# 04.net
KiCad netlist of a schematic drawn in Altium Designer
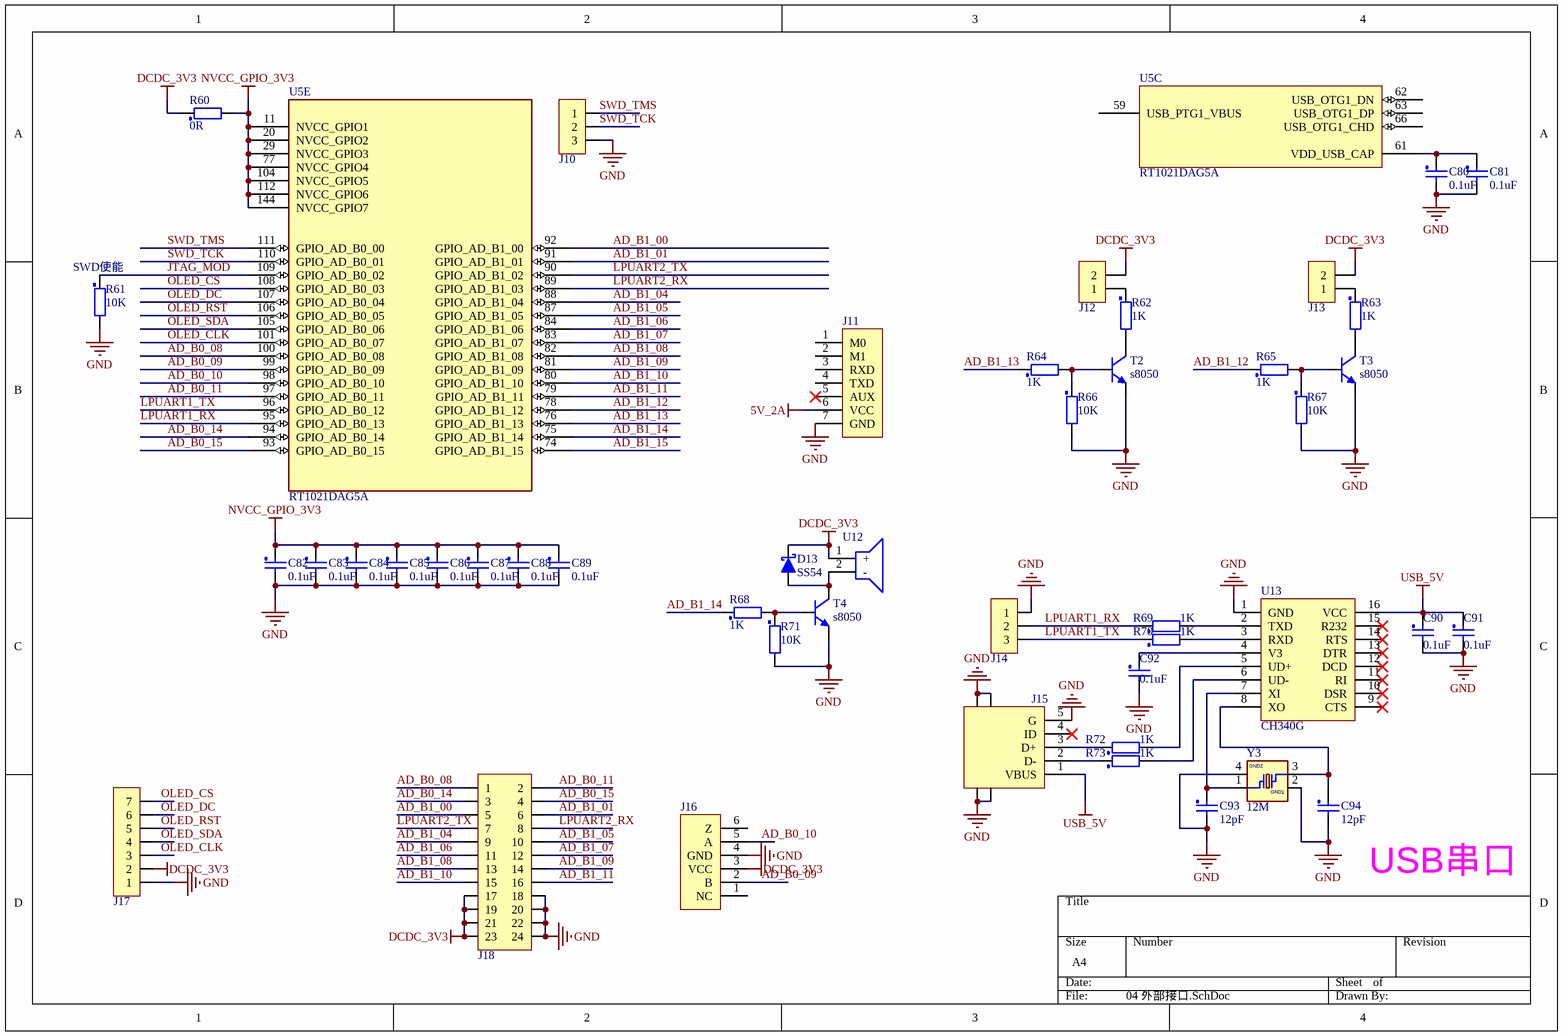
[diagram p0: 04 外部接口.SchDoc]

(export (version "E")
  (design (tool "Eeschema 10.0.6"))
  (components
    (comp (ref "C80")
      (value "0.1uF")
      (footprint "cap0603")
      (description "贴片电容")
      (fields (field (name "PUBLISHER") "Altium Limited"))
      (libsource (lib "元件库") (part "Cap"))
    )
    (comp (ref "C81")
      (value "0.1uF")
      (footprint "cap0603")
      (description "贴片电容")
      (fields (field (name "PUBLISHER") "Altium Limited"))
      (libsource (lib "元件库") (part "Cap"))
    )
    (comp (ref "C82")
      (value "0.1uF")
      (footprint "cap0603")
      (description "贴片电容")
      (fields (field (name "PUBLISHER") "Altium Limited"))
      (libsource (lib "元件库") (part "Cap"))
    )
    (comp (ref "C83")
      (value "0.1uF")
      (footprint "cap0603")
      (description "贴片电容")
      (fields (field (name "PUBLISHER") "Altium Limited"))
      (libsource (lib "元件库") (part "Cap"))
    )
    (comp (ref "C84")
      (value "0.1uF")
      (footprint "cap0603")
      (description "贴片电容")
      (fields (field (name "PUBLISHER") "Altium Limited"))
      (libsource (lib "元件库") (part "Cap"))
    )
    (comp (ref "C85")
      (value "0.1uF")
      (footprint "cap0603")
      (description "贴片电容")
      (fields (field (name "PUBLISHER") "Altium Limited"))
      (libsource (lib "元件库") (part "Cap"))
    )
    (comp (ref "C86")
      (value "0.1uF")
      (footprint "cap0603")
      (description "贴片电容")
      (fields (field (name "PUBLISHER") "Altium Limited"))
      (libsource (lib "元件库") (part "Cap"))
    )
    (comp (ref "C87")
      (value "0.1uF")
      (footprint "cap0603")
      (description "贴片电容")
      (fields (field (name "PUBLISHER") "Altium Limited"))
      (libsource (lib "元件库") (part "Cap"))
    )
    (comp (ref "C88")
      (value "0.1uF")
      (footprint "cap0603")
      (description "贴片电容")
      (fields (field (name "PUBLISHER") "Altium Limited"))
      (libsource (lib "元件库") (part "Cap"))
    )
    (comp (ref "C89")
      (value "0.1uF")
      (footprint "cap0603")
      (description "贴片电容")
      (fields (field (name "PUBLISHER") "Altium Limited"))
      (libsource (lib "元件库") (part "Cap"))
    )
    (comp (ref "C90")
      (value "0.1uF")
      (footprint "cap0603")
      (description "贴片电容")
      (fields (field (name "PUBLISHER") "Altium Limited"))
      (libsource (lib "元件库") (part "Cap"))
    )
    (comp (ref "C91")
      (value "0.1uF")
      (footprint "cap0603")
      (description "贴片电容")
      (fields (field (name "PUBLISHER") "Altium Limited"))
      (libsource (lib "元件库") (part "Cap"))
    )
    (comp (ref "C92")
      (value "0.1uF")
      (footprint "cap0603")
      (description "贴片电容")
      (fields (field (name "PUBLISHER") "Altium Limited"))
      (libsource (lib "元件库") (part "Cap"))
    )
    (comp (ref "C93")
      (value "12pF")
      (footprint "cap0603")
      (description "贴片电容")
      (fields (field (name "PUBLISHER") "Altium Limited"))
      (libsource (lib "元件库") (part "Cap"))
    )
    (comp (ref "C94")
      (value "12pF")
      (footprint "cap0603")
      (description "贴片电容")
      (fields (field (name "PUBLISHER") "Altium Limited"))
      (libsource (lib "元件库") (part "Cap"))
    )
    (comp (ref "D13")
      (value "SS54")
      (footprint "SMA(DO-214AC)")
      (description "肖特基二极管")
      (fields (field (name "PUBLISHER") "Altium Limited"))
      (libsource (lib "元件库") (part "D Schottky"))
    )
    (comp (ref "J10")
      (value "1X3")
      (footprint "HDR-1X3_SWD")
      (description "2.54mm公排针")
      (fields (field (name "版权归属") "源创客"))
      (libsource (lib "元件库") (part "Header 3"))
    )
    (comp (ref "J11")
      (value "1x7m")
      (footprint "uart_nrf24l01")
      (description "2.54mm母排座")
      (libsource (lib "元件库") (part "无线串口模块"))
    )
    (comp (ref "J12")
      (value "1x2")
      (footprint "HDR-1X2")
      (description "2.54mm公排针")
      (fields (field (name "版权归属") "源创客"))
      (libsource (lib "元件库") (part "Header 2"))
    )
    (comp (ref "J13")
      (value "1x2")
      (footprint "HDR-1X2")
      (description "2.54mm公排针")
      (fields (field (name "版权归属") "源创客"))
      (libsource (lib "元件库") (part "Header 2"))
    )
    (comp (ref "J14")
      (value "1X3")
      (footprint "HDR-1X3")
      (description "2.54mm公排针")
      (fields (field (name "版权归属") "源创客"))
      (libsource (lib "元件库") (part "Header 3"))
    )
    (comp (ref "J15")
      (value "USB_micro_b")
      (footprint "USB_micro_b")
      (description "microUSB母座,立创商城C404969")
      (libsource (lib "元件库") (part "USB_micro_b"))
    )
    (comp (ref "J16")
      (value "2x3")
      (footprint "LQ256Encoder")
      (description "2.54mm公排针")
      (libsource (lib "元件库") (part "LQ_AB256"))
    )
    (comp (ref "J17")
      (value "1X5m")
      (footprint "LQ_OLED128X64去丝印")
      (description "2.54mm母排座")
      (fields (field (name "版权归属") "源创客"))
      (libsource (lib "元件库") (part "Header 7"))
    )
    (comp (ref "J18")
      (value "2x12")
      (footprint "HDR-2x12")
      (description "2.54mm公排针")
      (fields (field (name "版权归属") "源创客"))
      (libsource (lib "元件库") (part "Header 12*2"))
    )
    (comp (ref "R60")
      (value "0R")
      (footprint "res0603")
      (description "贴片电阻")
      (fields (field (name "PUBLISHER") "Altium Limited"))
      (libsource (lib "") (part "Res_1"))
    )
    (comp (ref "R61")
      (value "10K")
      (footprint "res0603")
      (description "贴片电阻")
      (fields (field (name "PUBLISHER") "Altium Limited"))
      (libsource (lib "元件库") (part "Res"))
    )
    (comp (ref "R62")
      (value "1K")
      (footprint "res0603")
      (description "贴片电阻")
      (fields (field (name "PUBLISHER") "Altium Limited"))
      (libsource (lib "元件库") (part "Res"))
    )
    (comp (ref "R63")
      (value "1K")
      (footprint "res0603")
      (description "贴片电阻")
      (fields (field (name "PUBLISHER") "Altium Limited"))
      (libsource (lib "元件库") (part "Res"))
    )
    (comp (ref "R64")
      (value "1K")
      (footprint "res0603")
      (description "贴片电阻")
      (fields (field (name "PUBLISHER") "Altium Limited"))
      (libsource (lib "") (part "Res_1"))
    )
    (comp (ref "R65")
      (value "1K")
      (footprint "res0603")
      (description "贴片电阻")
      (fields (field (name "PUBLISHER") "Altium Limited"))
      (libsource (lib "") (part "Res_1"))
    )
    (comp (ref "R66")
      (value "10K")
      (footprint "res0603")
      (description "贴片电阻")
      (fields (field (name "PUBLISHER") "Altium Limited"))
      (libsource (lib "元件库") (part "Res"))
    )
    (comp (ref "R67")
      (value "10K")
      (footprint "res0603")
      (description "贴片电阻")
      (fields (field (name "PUBLISHER") "Altium Limited"))
      (libsource (lib "元件库") (part "Res"))
    )
    (comp (ref "R68")
      (value "1K")
      (footprint "res0603")
      (description "贴片电阻")
      (fields (field (name "PUBLISHER") "Altium Limited"))
      (libsource (lib "") (part "Res_1"))
    )
    (comp (ref "R69")
      (value "1K")
      (footprint "res0603")
      (description "贴片电阻")
      (fields (field (name "PUBLISHER") "Altium Limited"))
      (libsource (lib "") (part "Res_1"))
    )
    (comp (ref "R70")
      (value "1K")
      (footprint "res0603")
      (description "贴片电阻")
      (fields (field (name "PUBLISHER") "Altium Limited"))
      (libsource (lib "") (part "Res_1"))
    )
    (comp (ref "R71")
      (value "10K")
      (footprint "res0603")
      (description "贴片电阻")
      (fields (field (name "PUBLISHER") "Altium Limited"))
      (libsource (lib "元件库") (part "Res"))
    )
    (comp (ref "R72")
      (value "1K")
      (footprint "res0603")
      (description "贴片电阻")
      (fields (field (name "PUBLISHER") "Altium Limited"))
      (libsource (lib "") (part "Res_1"))
    )
    (comp (ref "R73")
      (value "1K")
      (footprint "res0603")
      (description "贴片电阻")
      (fields (field (name "PUBLISHER") "Altium Limited"))
      (libsource (lib "") (part "Res_1"))
    )
    (comp (ref "T2")
      (value "s8050")
      (footprint "SOT-23-3")
      (description "贴片三极管 NPN管")
      (libsource (lib "元件库") (part "s8050"))
    )
    (comp (ref "T3")
      (value "s8050")
      (footprint "SOT-23-3")
      (description "贴片三极管 NPN管")
      (libsource (lib "元件库") (part "s8050"))
    )
    (comp (ref "T4")
      (value "s8050")
      (footprint "SOT-23-3")
      (description "贴片三极管 NPN管")
      (libsource (lib "元件库") (part "s8050"))
    )
    (comp (ref "U5")
      (value "RT1021DAG5A")
      (footprint "LQFP144_0P5_20X20MM")
      (description "Cortex-M7 500MHZ 1.3V")
      (libsource (lib "元件库") (part "RT1021DAG5A"))
    )
    (comp (ref "U12")
      (value "beep")
      (footprint "beep")
      (description "有源蜂鸣器，3V，直径9mm引脚间距5mm")
      (libsource (lib "元件库") (part "beep"))
    )
    (comp (ref "U13")
      (value "CH340G")
      (footprint "SOP-16_150mil")
      (description "USB转串口芯片")
      (libsource (lib "元件库") (part "CH340G"))
    )
    (comp (ref "Y3")
      (value "12M")
      (footprint "SMD3225")
      (description "无源晶振 12MHZ 12pF 3.2X2.5MM SMD")
      (libsource (lib "元件库") (part "CRYSTAL_JXS63"))
    )
  )
  (nets
    (net (code "1") (name "/AD_B0_08") (class "Default")
      (node (ref "J18") (pin "1") (pinfunction "1_1") (pintype "passive"))
      (node (ref "U5") (pin "100") (pinfunction "GPIO_AD_B0_08_100") (pintype "bidirectional"))
    )
    (net (code "2") (name "/AD_B0_09") (class "Default")
      (node (ref "J16") (pin "2") (pinfunction "B_2") (pintype "passive"))
      (node (ref "U5") (pin "99") (pinfunction "GPIO_AD_B0_09_99") (pintype "bidirectional"))
    )
    (net (code "3") (name "/AD_B0_10") (class "Default")
      (node (ref "J16") (pin "5") (pinfunction "A_5") (pintype "passive"))
      (node (ref "U5") (pin "98") (pinfunction "GPIO_AD_B0_10_98") (pintype "bidirectional"))
    )
    (net (code "4") (name "/AD_B0_11") (class "Default")
      (node (ref "J18") (pin "2") (pinfunction "2_2") (pintype "passive"))
      (node (ref "U5") (pin "97") (pinfunction "GPIO_AD_B0_11_97") (pintype "bidirectional"))
    )
    (net (code "5") (name "/AD_B0_14") (class "Default")
      (node (ref "J18") (pin "3") (pinfunction "3_3") (pintype "passive"))
      (node (ref "U5") (pin "94") (pinfunction "GPIO_AD_B0_14_94") (pintype "bidirectional"))
    )
    (net (code "6") (name "/AD_B0_15") (class "Default")
      (node (ref "J18") (pin "4") (pinfunction "4_4") (pintype "passive"))
      (node (ref "U5") (pin "93") (pinfunction "GPIO_AD_B0_15_93") (pintype "bidirectional"))
    )
    (net (code "7") (name "/AD_B1_00") (class "Default")
      (node (ref "J18") (pin "5") (pinfunction "5_5") (pintype "passive"))
      (node (ref "U5") (pin "92") (pinfunction "GPIO_AD_B1_00_92") (pintype "bidirectional"))
    )
    (net (code "8") (name "/AD_B1_01") (class "Default")
      (node (ref "J18") (pin "6") (pinfunction "6_6") (pintype "passive"))
      (node (ref "U5") (pin "91") (pinfunction "GPIO_AD_B1_01_91") (pintype "bidirectional"))
    )
    (net (code "9") (name "/AD_B1_04") (class "Default")
      (node (ref "J18") (pin "9") (pinfunction "9_9") (pintype "passive"))
      (node (ref "U5") (pin "88") (pinfunction "GPIO_AD_B1_04_88") (pintype "bidirectional"))
    )
    (net (code "10") (name "/AD_B1_05") (class "Default")
      (node (ref "J18") (pin "10") (pinfunction "10_10") (pintype "passive"))
      (node (ref "U5") (pin "87") (pinfunction "GPIO_AD_B1_05_87") (pintype "bidirectional"))
    )
    (net (code "11") (name "/AD_B1_06") (class "Default")
      (node (ref "J18") (pin "11") (pinfunction "11_11") (pintype "passive"))
      (node (ref "U5") (pin "84") (pinfunction "GPIO_AD_B1_06_84") (pintype "bidirectional"))
    )
    (net (code "12") (name "/AD_B1_07") (class "Default")
      (node (ref "J18") (pin "12") (pinfunction "12_12") (pintype "passive"))
      (node (ref "U5") (pin "83") (pinfunction "GPIO_AD_B1_07_83") (pintype "bidirectional"))
    )
    (net (code "13") (name "/AD_B1_08") (class "Default")
      (node (ref "J18") (pin "13") (pinfunction "13_13") (pintype "passive"))
      (node (ref "U5") (pin "82") (pinfunction "GPIO_AD_B1_08_82") (pintype "bidirectional"))
    )
    (net (code "14") (name "/AD_B1_09") (class "Default")
      (node (ref "J18") (pin "14") (pinfunction "14_14") (pintype "passive"))
      (node (ref "U5") (pin "81") (pinfunction "GPIO_AD_B1_09_81") (pintype "bidirectional"))
    )
    (net (code "15") (name "/AD_B1_10") (class "Default")
      (node (ref "J18") (pin "15") (pinfunction "15_15") (pintype "passive"))
      (node (ref "U5") (pin "80") (pinfunction "GPIO_AD_B1_10_80") (pintype "bidirectional"))
    )
    (net (code "16") (name "/AD_B1_11") (class "Default")
      (node (ref "J18") (pin "16") (pinfunction "16_16") (pintype "passive"))
      (node (ref "U5") (pin "79") (pinfunction "GPIO_AD_B1_11_79") (pintype "bidirectional"))
    )
    (net (code "17") (name "/AD_B1_12") (class "Default")
      (node (ref "R65") (pin "1") (pinfunction "1_1") (pintype "passive"))
      (node (ref "U5") (pin "78") (pinfunction "GPIO_AD_B1_12_78") (pintype "bidirectional"))
    )
    (net (code "18") (name "/AD_B1_13") (class "Default")
      (node (ref "R64") (pin "1") (pinfunction "1_1") (pintype "passive"))
      (node (ref "U5") (pin "76") (pinfunction "GPIO_AD_B1_13_76") (pintype "bidirectional"))
    )
    (net (code "19") (name "/AD_B1_14") (class "Default")
      (node (ref "R68") (pin "1") (pinfunction "1_1") (pintype "passive"))
      (node (ref "U5") (pin "75") (pinfunction "GPIO_AD_B1_14_75") (pintype "bidirectional"))
    )
    (net (code "20") (name "/AD_B1_15") (class "Default")
      (node (ref "U5") (pin "74") (pinfunction "GPIO_AD_B1_15_74") (pintype "bidirectional"))
    )
    (net (code "21") (name "/JTAG_MOD") (class "Default")
      (node (ref "R61") (pin "1") (pinfunction "1_1") (pintype "passive"))
      (node (ref "U5") (pin "109") (pinfunction "GPIO_AD_B0_02_109") (pintype "bidirectional"))
    )
    (net (code "22") (name "/LPUART1_RX") (class "Default")
      (node (ref "J14") (pin "2") (pinfunction "2_2") (pintype "passive"))
      (node (ref "R69") (pin "1") (pinfunction "1_1") (pintype "passive"))
      (node (ref "U5") (pin "95") (pinfunction "GPIO_AD_B0_13_95") (pintype "bidirectional"))
    )
    (net (code "23") (name "/LPUART1_TX") (class "Default")
      (node (ref "J14") (pin "3") (pinfunction "3_3") (pintype "passive"))
      (node (ref "R70") (pin "1") (pinfunction "1_1") (pintype "passive"))
      (node (ref "U5") (pin "96") (pinfunction "GPIO_AD_B0_12_96") (pintype "bidirectional"))
    )
    (net (code "24") (name "/LPUART2_RX") (class "Default")
      (node (ref "J18") (pin "8") (pinfunction "8_8") (pintype "passive"))
      (node (ref "U5") (pin "89") (pinfunction "GPIO_AD_B1_03_89") (pintype "bidirectional"))
    )
    (net (code "25") (name "/LPUART2_TX") (class "Default")
      (node (ref "J18") (pin "7") (pinfunction "7_7") (pintype "passive"))
      (node (ref "U5") (pin "90") (pinfunction "GPIO_AD_B1_02_90") (pintype "bidirectional"))
    )
    (net (code "26") (name "/OLED_CLK") (class "Default")
      (node (ref "J17") (pin "3") (pinfunction "3_3") (pintype "passive"))
      (node (ref "U5") (pin "101") (pinfunction "GPIO_AD_B0_07_101") (pintype "bidirectional"))
    )
    (net (code "27") (name "/OLED_CS") (class "Default")
      (node (ref "J17") (pin "7") (pinfunction "7_7") (pintype "passive"))
      (node (ref "U5") (pin "108") (pinfunction "GPIO_AD_B0_03_108") (pintype "bidirectional"))
    )
    (net (code "28") (name "/OLED_DC") (class "Default")
      (node (ref "J17") (pin "6") (pinfunction "6_6") (pintype "passive"))
      (node (ref "U5") (pin "107") (pinfunction "GPIO_AD_B0_04_107") (pintype "bidirectional"))
    )
    (net (code "29") (name "/OLED_RST") (class "Default")
      (node (ref "J17") (pin "5") (pinfunction "5_5") (pintype "passive"))
      (node (ref "U5") (pin "106") (pinfunction "GPIO_AD_B0_05_106") (pintype "bidirectional"))
    )
    (net (code "30") (name "/OLED_SDA") (class "Default")
      (node (ref "J17") (pin "4") (pinfunction "4_4") (pintype "passive"))
      (node (ref "U5") (pin "105") (pinfunction "GPIO_AD_B0_06_105") (pintype "bidirectional"))
    )
    (net (code "31") (name "/SWD_TCK") (class "Default")
      (node (ref "J10") (pin "2") (pinfunction "2_2") (pintype "passive"))
      (node (ref "U5") (pin "110") (pinfunction "GPIO_AD_B0_01_110") (pintype "bidirectional"))
    )
    (net (code "32") (name "/SWD_TMS") (class "Default")
      (node (ref "J10") (pin "1") (pinfunction "1_1") (pintype "passive"))
      (node (ref "U5") (pin "111") (pinfunction "GPIO_AD_B0_00_111") (pintype "bidirectional"))
    )
    (net (code "33") (name "5V_2A") (class "Default")
      (node (ref "J11") (pin "6") (pinfunction "VCC_6") (pintype "passive"))
    )
    (net (code "34") (name "DCDC_3V3") (class "Default")
      (node (ref "D13") (pin "2") (pinfunction "K_2") (pintype "passive"))
      (node (ref "J12") (pin "2") (pinfunction "2_2") (pintype "passive"))
      (node (ref "J13") (pin "2") (pinfunction "2_2") (pintype "passive"))
      (node (ref "J16") (pin "3") (pinfunction "VCC_3") (pintype "passive"))
      (node (ref "J17") (pin "2") (pinfunction "2_2") (pintype "passive"))
      (node (ref "J18") (pin "17") (pinfunction "17_17") (pintype "passive"))
      (node (ref "J18") (pin "19") (pinfunction "19_19") (pintype "passive"))
      (node (ref "J18") (pin "21") (pinfunction "21_21") (pintype "passive"))
      (node (ref "J18") (pin "23") (pinfunction "23_23") (pintype "passive"))
      (node (ref "R60") (pin "1") (pinfunction "1_1") (pintype "passive"))
      (node (ref "U12") (pin "1") (pinfunction "+_1") (pintype "passive"))
    )
    (net (code "35") (name "GND") (class "Default")
      (node (ref "C80") (pin "2") (pinfunction "2_2") (pintype "passive"))
      (node (ref "C81") (pin "2") (pinfunction "2_2") (pintype "passive"))
      (node (ref "C82") (pin "2") (pinfunction "2_2") (pintype "passive"))
      (node (ref "C83") (pin "2") (pinfunction "2_2") (pintype "passive"))
      (node (ref "C84") (pin "2") (pinfunction "2_2") (pintype "passive"))
      (node (ref "C85") (pin "2") (pinfunction "2_2") (pintype "passive"))
      (node (ref "C86") (pin "2") (pinfunction "2_2") (pintype "passive"))
      (node (ref "C87") (pin "2") (pinfunction "2_2") (pintype "passive"))
      (node (ref "C88") (pin "2") (pinfunction "2_2") (pintype "passive"))
      (node (ref "C89") (pin "2") (pinfunction "2_2") (pintype "passive"))
      (node (ref "C90") (pin "2") (pinfunction "2_2") (pintype "passive"))
      (node (ref "C91") (pin "2") (pinfunction "2_2") (pintype "passive"))
      (node (ref "C92") (pin "2") (pinfunction "2_2") (pintype "passive"))
      (node (ref "C93") (pin "2") (pinfunction "2_2") (pintype "passive"))
      (node (ref "C94") (pin "2") (pinfunction "2_2") (pintype "passive"))
      (node (ref "J10") (pin "3") (pinfunction "3_3") (pintype "passive"))
      (node (ref "J11") (pin "7") (pinfunction "GND_7") (pintype "passive"))
      (node (ref "J14") (pin "1") (pinfunction "1_1") (pintype "passive"))
      (node (ref "J15") (pin "5") (pinfunction "G_5") (pintype "passive"))
      (node (ref "J15") (pin "6") (pinfunction "6_6") (pintype "passive"))
      (node (ref "J15") (pin "7") (pinfunction "7_7") (pintype "passive"))
      (node (ref "J15") (pin "8") (pinfunction "8_8") (pintype "passive"))
      (node (ref "J15") (pin "9") (pinfunction "9_9") (pintype "passive"))
      (node (ref "J16") (pin "4") (pinfunction "GND_4") (pintype "passive"))
      (node (ref "J17") (pin "1") (pinfunction "1_1") (pintype "passive"))
      (node (ref "J18") (pin "18") (pinfunction "18_18") (pintype "passive"))
      (node (ref "J18") (pin "20") (pinfunction "20_20") (pintype "passive"))
      (node (ref "J18") (pin "22") (pinfunction "22_22") (pintype "passive"))
      (node (ref "J18") (pin "24") (pinfunction "24_24") (pintype "passive"))
      (node (ref "R61") (pin "2") (pinfunction "2_2") (pintype "passive"))
      (node (ref "R66") (pin "2") (pinfunction "2_2") (pintype "passive"))
      (node (ref "R67") (pin "2") (pinfunction "2_2") (pintype "passive"))
      (node (ref "R71") (pin "2") (pinfunction "2_2") (pintype "passive"))
      (node (ref "T2") (pin "2") (pinfunction "E_2") (pintype "passive"))
      (node (ref "T3") (pin "2") (pinfunction "E_2") (pintype "passive"))
      (node (ref "T4") (pin "2") (pinfunction "E_2") (pintype "passive"))
      (node (ref "U13") (pin "1") (pinfunction "GND_1") (pintype "passive"))
      (node (ref "Y3") (pin "2") (pinfunction "GND1_2") (pintype "power_in"))
      (node (ref "Y3") (pin "4") (pinfunction "GND2_4") (pintype "power_in"))
    )
    (net (code "36") (name "NVCC_GPIO_3V3") (class "Default")
      (node (ref "C82") (pin "1") (pinfunction "1_1") (pintype "passive"))
      (node (ref "C83") (pin "1") (pinfunction "1_1") (pintype "passive"))
      (node (ref "C84") (pin "1") (pinfunction "1_1") (pintype "passive"))
      (node (ref "C85") (pin "1") (pinfunction "1_1") (pintype "passive"))
      (node (ref "C86") (pin "1") (pinfunction "1_1") (pintype "passive"))
      (node (ref "C87") (pin "1") (pinfunction "1_1") (pintype "passive"))
      (node (ref "C88") (pin "1") (pinfunction "1_1") (pintype "passive"))
      (node (ref "C89") (pin "1") (pinfunction "1_1") (pintype "passive"))
      (node (ref "R60") (pin "2") (pinfunction "2_2") (pintype "passive"))
      (node (ref "U5") (pin "104") (pinfunction "NVCC_GPIO5_104") (pintype "power_in"))
      (node (ref "U5") (pin "11") (pinfunction "NVCC_GPIO1_11") (pintype "power_in"))
      (node (ref "U5") (pin "112") (pinfunction "NVCC_GPIO6_112") (pintype "power_in"))
      (node (ref "U5") (pin "144") (pinfunction "NVCC_GPIO7_144") (pintype "power_in"))
      (node (ref "U5") (pin "20") (pinfunction "NVCC_GPIO2_20") (pintype "power_in"))
      (node (ref "U5") (pin "29") (pinfunction "NVCC_GPIO3_29") (pintype "power_in"))
      (node (ref "U5") (pin "77") (pinfunction "NVCC_GPIO4_77") (pintype "power_in"))
    )
    (net (code "37") (name "Net-(D13-A)") (class "Default")
      (node (ref "D13") (pin "1") (pinfunction "A_1") (pintype "passive"))
      (node (ref "T4") (pin "3") (pinfunction "C_3") (pintype "passive"))
      (node (ref "U12") (pin "2") (pinfunction "-_2") (pintype "passive"))
    )
    (net (code "38") (name "Net-(J12-Pad1)") (class "Default")
      (node (ref "J12") (pin "1") (pinfunction "1_1") (pintype "passive"))
      (node (ref "R62") (pin "1") (pinfunction "1_1") (pintype "passive"))
    )
    (net (code "39") (name "Net-(J13-Pad1)") (class "Default")
      (node (ref "J13") (pin "1") (pinfunction "1_1") (pintype "passive"))
      (node (ref "R63") (pin "1") (pinfunction "1_1") (pintype "passive"))
    )
    (net (code "40") (name "Net-(J15-D+)") (class "Default")
      (node (ref "J15") (pin "3") (pinfunction "D+_3") (pintype "passive"))
      (node (ref "R72") (pin "1") (pinfunction "1_1") (pintype "passive"))
    )
    (net (code "41") (name "Net-(J15-D-)") (class "Default")
      (node (ref "J15") (pin "2") (pinfunction "D-_2") (pintype "passive"))
      (node (ref "R73") (pin "1") (pinfunction "1_1") (pintype "passive"))
    )
    (net (code "42") (name "Net-(T2-B)") (class "Default")
      (node (ref "R64") (pin "2") (pinfunction "2_2") (pintype "passive"))
      (node (ref "R66") (pin "1") (pinfunction "1_1") (pintype "passive"))
      (node (ref "T2") (pin "1") (pinfunction "B_1") (pintype "passive"))
    )
    (net (code "43") (name "Net-(T2-C)") (class "Default")
      (node (ref "R62") (pin "2") (pinfunction "2_2") (pintype "passive"))
      (node (ref "T2") (pin "3") (pinfunction "C_3") (pintype "passive"))
    )
    (net (code "44") (name "Net-(T3-B)") (class "Default")
      (node (ref "R65") (pin "2") (pinfunction "2_2") (pintype "passive"))
      (node (ref "R67") (pin "1") (pinfunction "1_1") (pintype "passive"))
      (node (ref "T3") (pin "1") (pinfunction "B_1") (pintype "passive"))
    )
    (net (code "45") (name "Net-(T3-C)") (class "Default")
      (node (ref "R63") (pin "2") (pinfunction "2_2") (pintype "passive"))
      (node (ref "T3") (pin "3") (pinfunction "C_3") (pintype "passive"))
    )
    (net (code "46") (name "Net-(T4-B)") (class "Default")
      (node (ref "R68") (pin "2") (pinfunction "2_2") (pintype "passive"))
      (node (ref "R71") (pin "1") (pinfunction "1_1") (pintype "passive"))
      (node (ref "T4") (pin "1") (pinfunction "B_1") (pintype "passive"))
    )
    (net (code "47") (name "Net-(U5C-VDD_USB_CAP)") (class "Default")
      (node (ref "C80") (pin "1") (pinfunction "1_1") (pintype "passive"))
      (node (ref "C81") (pin "1") (pinfunction "1_1") (pintype "passive"))
      (node (ref "U5") (pin "61") (pinfunction "VDD_USB_CAP_61") (pintype "passive"))
    )
    (net (code "48") (name "Net-(U13-RXD)") (class "Default")
      (node (ref "R70") (pin "2") (pinfunction "2_2") (pintype "passive"))
      (node (ref "U13") (pin "3") (pinfunction "RXD_3") (pintype "passive"))
    )
    (net (code "49") (name "Net-(U13-TXD)") (class "Default")
      (node (ref "R69") (pin "2") (pinfunction "2_2") (pintype "passive"))
      (node (ref "U13") (pin "2") (pinfunction "TXD_2") (pintype "passive"))
    )
    (net (code "50") (name "Net-(U13-UD+)") (class "Default")
      (node (ref "R72") (pin "2") (pinfunction "2_2") (pintype "passive"))
      (node (ref "U13") (pin "5") (pinfunction "UD+_5") (pintype "passive"))
    )
    (net (code "51") (name "Net-(U13-UD-)") (class "Default")
      (node (ref "R73") (pin "2") (pinfunction "2_2") (pintype "passive"))
      (node (ref "U13") (pin "6") (pinfunction "UD-_6") (pintype "passive"))
    )
    (net (code "52") (name "Net-(U13-V3)") (class "Default")
      (node (ref "C92") (pin "1") (pinfunction "1_1") (pintype "passive"))
      (node (ref "U13") (pin "4") (pinfunction "V3_4") (pintype "passive"))
    )
    (net (code "53") (name "Net-(U13-XI)") (class "Default")
      (node (ref "C93") (pin "1") (pinfunction "1_1") (pintype "passive"))
      (node (ref "U13") (pin "7") (pinfunction "XI_7") (pintype "passive"))
      (node (ref "Y3") (pin "1") (pinfunction "1_1") (pintype "passive"))
    )
    (net (code "54") (name "Net-(U13-XO)") (class "Default")
      (node (ref "C94") (pin "1") (pinfunction "1_1") (pintype "passive"))
      (node (ref "U13") (pin "8") (pinfunction "XO_8") (pintype "passive"))
      (node (ref "Y3") (pin "3") (pinfunction "3_3") (pintype "passive"))
    )
    (net (code "55") (name "USB_5V") (class "Default")
      (node (ref "C90") (pin "1") (pinfunction "1_1") (pintype "passive"))
      (node (ref "C91") (pin "1") (pinfunction "1_1") (pintype "passive"))
      (node (ref "J15") (pin "1") (pinfunction "VBUS_1") (pintype "passive"))
      (node (ref "U13") (pin "16") (pinfunction "VCC_16") (pintype "passive"))
    )
    (net (code "56") (name "unconnected-(J11-AUX-Pad5)") (class "Default")
      (node (ref "J11") (pin "5") (pinfunction "AUX_5") (pintype "passive+no_connect"))
    )
    (net (code "57") (name "unconnected-(J11-M0-Pad1)") (class "Default")
      (node (ref "J11") (pin "1") (pinfunction "M0_1") (pintype "passive"))
    )
    (net (code "58") (name "unconnected-(J11-M1-Pad2)") (class "Default")
      (node (ref "J11") (pin "2") (pinfunction "M1_2") (pintype "passive"))
    )
    (net (code "59") (name "unconnected-(J11-RXD-Pad3)") (class "Default")
      (node (ref "J11") (pin "3") (pinfunction "RXD_3") (pintype "passive"))
    )
    (net (code "60") (name "unconnected-(J11-TXD-Pad4)") (class "Default")
      (node (ref "J11") (pin "4") (pinfunction "TXD_4") (pintype "passive"))
    )
    (net (code "61") (name "unconnected-(J15-ID-Pad4)") (class "Default")
      (node (ref "J15") (pin "4") (pinfunction "ID_4") (pintype "passive+no_connect"))
    )
    (net (code "62") (name "unconnected-(J16-NC-Pad1)") (class "Default")
      (node (ref "J16") (pin "1") (pinfunction "NC_1") (pintype "passive"))
    )
    (net (code "63") (name "unconnected-(J16-Z-Pad6)") (class "Default")
      (node (ref "J16") (pin "6") (pinfunction "Z_6") (pintype "passive"))
    )
    (net (code "64") (name "unconnected-(U5C-USB_OTG1_CHD-Pad66)") (class "Default")
      (node (ref "U5") (pin "66") (pinfunction "USB_OTG1_CHD_66") (pintype "bidirectional"))
    )
    (net (code "65") (name "unconnected-(U5C-USB_OTG1_DN-Pad62)") (class "Default")
      (node (ref "U5") (pin "62") (pinfunction "USB_OTG1_DN_62") (pintype "bidirectional"))
    )
    (net (code "66") (name "unconnected-(U5C-USB_OTG1_DP-Pad63)") (class "Default")
      (node (ref "U5") (pin "63") (pinfunction "USB_OTG1_DP_63") (pintype "bidirectional"))
    )
    (net (code "67") (name "unconnected-(U5C-USB_PTG1_VBUS-Pad59)") (class "Default")
      (node (ref "U5") (pin "59") (pinfunction "USB_PTG1_VBUS_59") (pintype "passive"))
    )
    (net (code "68") (name "unconnected-(U13-CTS-Pad9)") (class "Default")
      (node (ref "U13") (pin "9") (pinfunction "CTS_9") (pintype "passive+no_connect"))
    )
    (net (code "69") (name "unconnected-(U13-DCD-Pad12)") (class "Default")
      (node (ref "U13") (pin "12") (pinfunction "DCD_12") (pintype "passive+no_connect"))
    )
    (net (code "70") (name "unconnected-(U13-DSR-Pad10)") (class "Default")
      (node (ref "U13") (pin "10") (pinfunction "DSR_10") (pintype "passive+no_connect"))
    )
    (net (code "71") (name "unconnected-(U13-DTR-Pad13)") (class "Default")
      (node (ref "U13") (pin "13") (pinfunction "DTR_13") (pintype "passive+no_connect"))
    )
    (net (code "72") (name "unconnected-(U13-R232-Pad15)") (class "Default")
      (node (ref "U13") (pin "15") (pinfunction "R232_15") (pintype "passive+no_connect"))
    )
    (net (code "73") (name "unconnected-(U13-RI-Pad11)") (class "Default")
      (node (ref "U13") (pin "11") (pinfunction "RI_11") (pintype "passive+no_connect"))
    )
    (net (code "74") (name "unconnected-(U13-RTS-Pad14)") (class "Default")
      (node (ref "U13") (pin "14") (pinfunction "RTS_14") (pintype "passive+no_connect"))
    )
  )
)
